# Glucometro_v2_schematic.net
KiCad netlist of a schematic drawn in Altium Designer
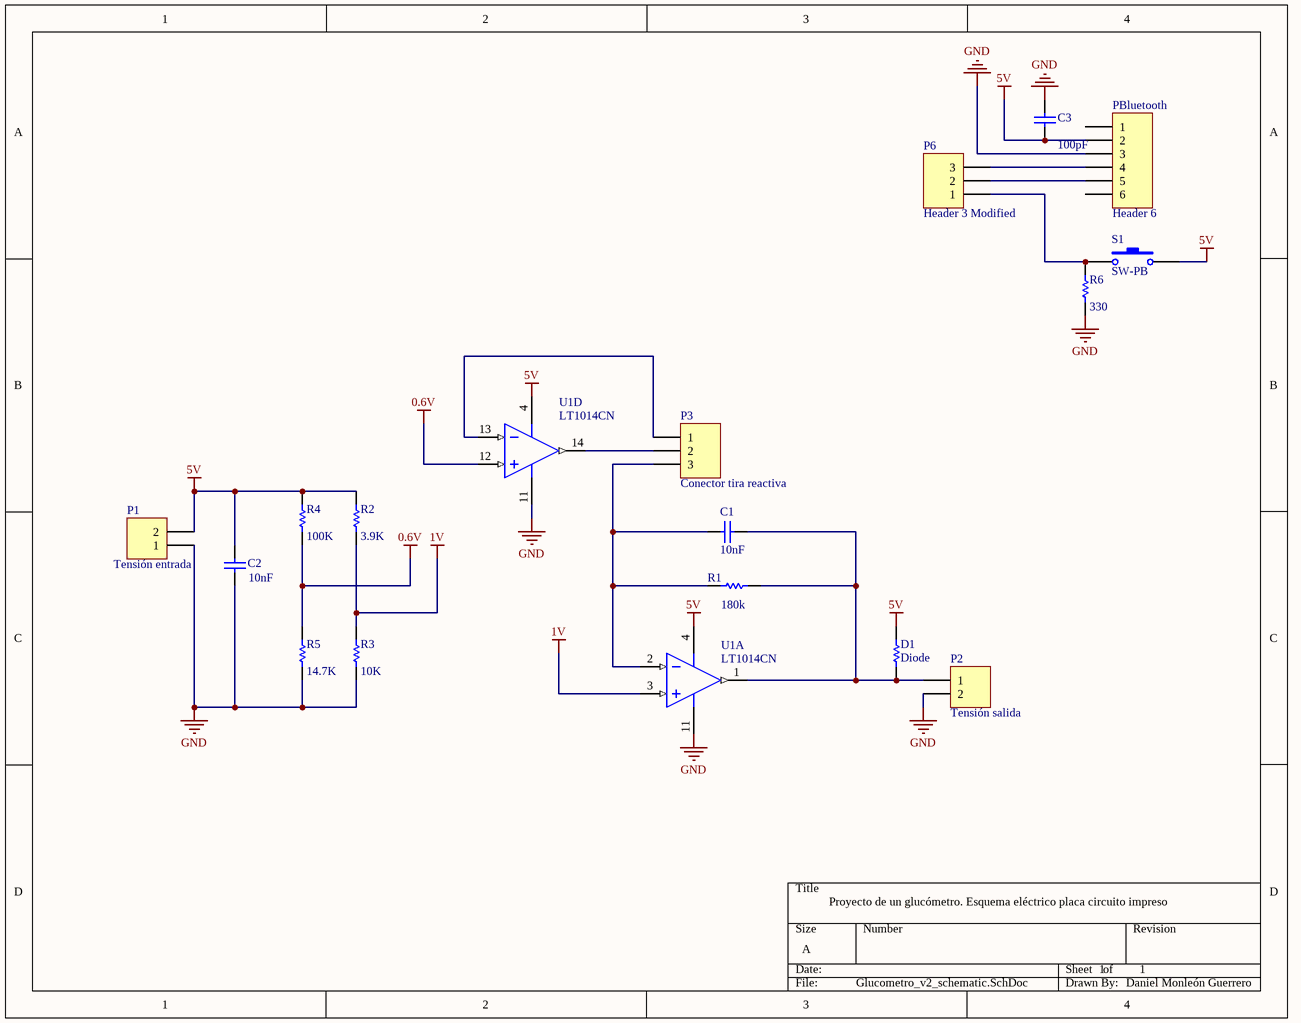
[diagram p0: Glucometro_v2_schematic.SchDoc]

(export (version "E")
  (design (tool "Eeschema 10.0.6"))
  (components
    (comp (ref "C1")
      (value "10nF")
      (footprint "CAP_EDITED")
      (description "Capacitor")
      (fields (field (name "Comment") "Cap Modified") (field (name "PUBLISHER") "Altium Limited"))
      (libsource (lib "Header_Edited_SchLib") (part "Cap"))
    )
    (comp (ref "C2")
      (value "10nF")
      (footprint "Header_Edited_PCBLib:CAP_ALIM_EDITED")
      (description "Capacitor")
      (fields (field (name "Comment") "Cap") (field (name "PUBLISHER") "Altium Limited"))
      (libsource (lib "Miscellaneous Devices") (part "Cap"))
    )
    (comp (ref "C3")
      (value "100pF")
      (footprint "Header_Edited_PCBLib:CAP_ALIM_EDITED")
      (description "Capacitor")
      (fields (field (name "Comment") "Cap") (field (name "PUBLISHER") "Altium Limited"))
      (libsource (lib "Miscellaneous Devices") (part "Cap"))
    )
    (comp (ref "D1")
      (value "Diode")
      (footprint "AXIAL-0.3")
      (description "Resistor")
      (fields (field (name "PUBLISHER") "Altium Limited"))
      (libsource (lib "Miscellaneous Devices") (part "Res1"))
    )
    (comp (ref "P1")
      (value "Tensión entrada")
      (footprint "Header2_edited")
      (description "Header, 2-Pin")
      (fields (field (name "PUBLISHER") "Altium Limited"))
      (libsource (lib "Header2c") (part "Header 2"))
    )
    (comp (ref "P2")
      (value "Tensión salida")
      (footprint "Header2_edited")
      (description "Header, 2-Pin")
      (fields (field (name "PUBLISHER") "Altium Limited"))
      (libsource (lib "Header_Edited_SchLib") (part "Header 2"))
    )
    (comp (ref "P3")
      (value "Conector tira reactiva")
      (footprint "HEADER3_EDITED")
      (description "Header, 3-Pin")
      (fields (field (name "PUBLISHER") "Altium Limited"))
      (libsource (lib "") (part "Header 3_1"))
    )
    (comp (ref "P6")
      (value "Header 3 Modified")
      (footprint "HEADER3_EDITED")
      (description "Header, 3-Pin")
      (fields (field (name "PUBLISHER") "Altium Limited"))
      (libsource (lib "Header_Edited_SchLib") (part "Header 3"))
    )
    (comp (ref "PBluetooth")
      (value "Header 6")
      (footprint "HEADERBLUETOOTH")
      (description "Header, 6-Pin")
      (fields (field (name "PUBLISHER") "Altium Limited"))
      (libsource (lib "Header_Edited_SchLib") (part "Header 6"))
    )
    (comp (ref "R1")
      (value "180k")
      (footprint "AXIAL-0.3")
      (description "Resistor")
      (fields (field (name "Comment") "Res1") (field (name "PUBLISHER") "Altium Limited"))
      (libsource (lib "Miscellaneous Devices") (part "Res1"))
    )
    (comp (ref "R2")
      (value "3.9K")
      (footprint "AXIAL-0.3")
      (description "Resistor")
      (fields (field (name "Comment") "Res1") (field (name "PUBLISHER") "Altium Limited"))
      (libsource (lib "Miscellaneous Devices") (part "Res1"))
    )
    (comp (ref "R3")
      (value "10K")
      (footprint "AXIAL-0.3")
      (description "Resistor")
      (fields (field (name "Comment") "Res1") (field (name "PUBLISHER") "Altium Limited"))
      (libsource (lib "Miscellaneous Devices") (part "Res1"))
    )
    (comp (ref "R4")
      (value "100K")
      (footprint "AXIAL-0.3")
      (description "Resistor")
      (fields (field (name "Comment") "Res1") (field (name "PUBLISHER") "Altium Limited"))
      (libsource (lib "Miscellaneous Devices") (part "Res1"))
    )
    (comp (ref "R5")
      (value "14.7K")
      (footprint "AXIAL-0.3")
      (description "Resistor")
      (fields (field (name "Comment") "Res1") (field (name "PUBLISHER") "Altium Limited"))
      (libsource (lib "Miscellaneous Devices") (part "Res1"))
    )
    (comp (ref "R6")
      (value "330")
      (footprint "AXIAL-0.3")
      (description "Resistor")
      (fields (field (name "Comment") "Res1") (field (name "PUBLISHER") "Altium Limited"))
      (libsource (lib "Miscellaneous Devices") (part "Res1"))
    )
    (comp (ref "S1")
      (value "SW-PB")
      (footprint "BUTTON")
      (description "Switch")
      (fields (field (name "PUBLISHER") "Altium Limited"))
      (libsource (lib "Header_Edited_SchLib") (part "Button"))
    )
    (comp (ref "U1")
      (value "LT1014CN")
      (footprint "LT-N-14")
      (fields
        (field (name "LINEAR TECHNOLOGY PART NUMBER") "LT1014")
        (field (name "MANUFACTURER") "Linear Technology")
      )
      (libsource (lib "Linear Technology Operational Amplifiers (LT1000)") (part "LT1014CN"))
    )
  )
  (nets
    (net (code "1") (name "0.6V") (class "Default")
      (node (ref "R4") (pin "1") (pinfunction "1_1") (pintype "passive"))
      (node (ref "R5") (pin "2") (pinfunction "2_2") (pintype "passive"))
      (node (ref "U1") (pin "12") (pinfunction "+IN_D_12") (pintype "input"))
    )
    (net (code "2") (name "1V") (class "Default")
      (node (ref "R2") (pin "1") (pinfunction "1_1") (pintype "passive"))
      (node (ref "R3") (pin "2") (pinfunction "2_2") (pintype "passive"))
      (node (ref "U1") (pin "3") (pinfunction "+IN_A_3") (pintype "input"))
    )
    (net (code "3") (name "5V") (class "Default")
      (node (ref "C2") (pin "2") (pinfunction "2_2") (pintype "passive"))
      (node (ref "C3") (pin "1") (pinfunction "1_1") (pintype "passive"))
      (node (ref "D1") (pin "2") (pinfunction "2_2") (pintype "passive"))
      (node (ref "P1") (pin "2") (pinfunction "2_2") (pintype "passive"))
      (node (ref "PBluetooth") (pin "2") (pinfunction "2_2") (pintype "passive"))
      (node (ref "R2") (pin "2") (pinfunction "2_2") (pintype "passive"))
      (node (ref "R4") (pin "2") (pinfunction "2_2") (pintype "passive"))
      (node (ref "S1") (pin "2") (pinfunction "2_2") (pintype "passive"))
      (node (ref "U1") (pin "4") (pinfunction "V+_4") (pintype "power_in"))
    )
    (net (code "4") (name "GND") (class "Default")
      (node (ref "C2") (pin "1") (pinfunction "1_1") (pintype "passive"))
      (node (ref "C3") (pin "2") (pinfunction "2_2") (pintype "passive"))
      (node (ref "P1") (pin "1") (pinfunction "1_1") (pintype "passive"))
      (node (ref "P2") (pin "2") (pinfunction "2_2") (pintype "passive"))
      (node (ref "PBluetooth") (pin "3") (pinfunction "3_3") (pintype "passive"))
      (node (ref "R3") (pin "1") (pinfunction "1_1") (pintype "passive"))
      (node (ref "R5") (pin "1") (pinfunction "1_1") (pintype "passive"))
      (node (ref "R6") (pin "1") (pinfunction "1_1") (pintype "passive"))
      (node (ref "U1") (pin "11") (pinfunction "V-_11") (pintype "power_in"))
    )
    (net (code "5") (name "Net-(P6-Pad1)") (class "Default")
      (node (ref "P6") (pin "1") (pinfunction "1_1") (pintype "passive"))
      (node (ref "R6") (pin "2") (pinfunction "2_2") (pintype "passive"))
      (node (ref "S1") (pin "1") (pinfunction "1_1") (pintype "passive"))
    )
    (net (code "6") (name "Net-(P6-Pad2)") (class "Default")
      (node (ref "P6") (pin "2") (pinfunction "2_2") (pintype "passive"))
      (node (ref "PBluetooth") (pin "5") (pinfunction "5_5") (pintype "passive"))
    )
    (net (code "7") (name "Net-(P6-Pad3)") (class "Default")
      (node (ref "P6") (pin "3") (pinfunction "3_3") (pintype "passive"))
      (node (ref "PBluetooth") (pin "4") (pinfunction "4_4") (pintype "passive"))
    )
    (net (code "8") (name "Net-(U1A--IN_A)") (class "Default")
      (node (ref "C1") (pin "1") (pinfunction "1_1") (pintype "passive"))
      (node (ref "P3") (pin "3") (pinfunction "3_3") (pintype "passive"))
      (node (ref "R1") (pin "1") (pinfunction "1_1") (pintype "passive"))
      (node (ref "U1") (pin "2") (pinfunction "-IN_A_2") (pintype "input"))
    )
    (net (code "9") (name "Net-(U1A-OUTPUT_A)") (class "Default")
      (node (ref "C1") (pin "2") (pinfunction "2_2") (pintype "passive"))
      (node (ref "D1") (pin "1") (pinfunction "1_1") (pintype "passive"))
      (node (ref "P2") (pin "1") (pinfunction "1_1") (pintype "passive"))
      (node (ref "R1") (pin "2") (pinfunction "2_2") (pintype "passive"))
      (node (ref "U1") (pin "1") (pinfunction "OUTPUT_A_1") (pintype "output"))
    )
    (net (code "10") (name "Net-(U1D--IN_D)") (class "Default")
      (node (ref "P3") (pin "1") (pinfunction "1_1") (pintype "passive"))
      (node (ref "U1") (pin "13") (pinfunction "-IN_D_13") (pintype "input"))
    )
    (net (code "11") (name "Net-(U1D-OUTPUT_D)") (class "Default")
      (node (ref "P3") (pin "2") (pinfunction "2_2") (pintype "passive"))
      (node (ref "U1") (pin "14") (pinfunction "OUTPUT_D_14") (pintype "output"))
    )
    (net (code "12") (name "unconnected-(PBluetooth-Pad1)") (class "Default")
      (node (ref "PBluetooth") (pin "1") (pinfunction "1_1") (pintype "passive"))
    )
    (net (code "13") (name "unconnected-(PBluetooth-Pad6)") (class "Default")
      (node (ref "PBluetooth") (pin "6") (pinfunction "6_6") (pintype "passive"))
    )
  )
)
